# Dual_linear_VCA_chip_v3_0_-_external_tri.net
KiCad netlist of a schematic drawn in EAGLE
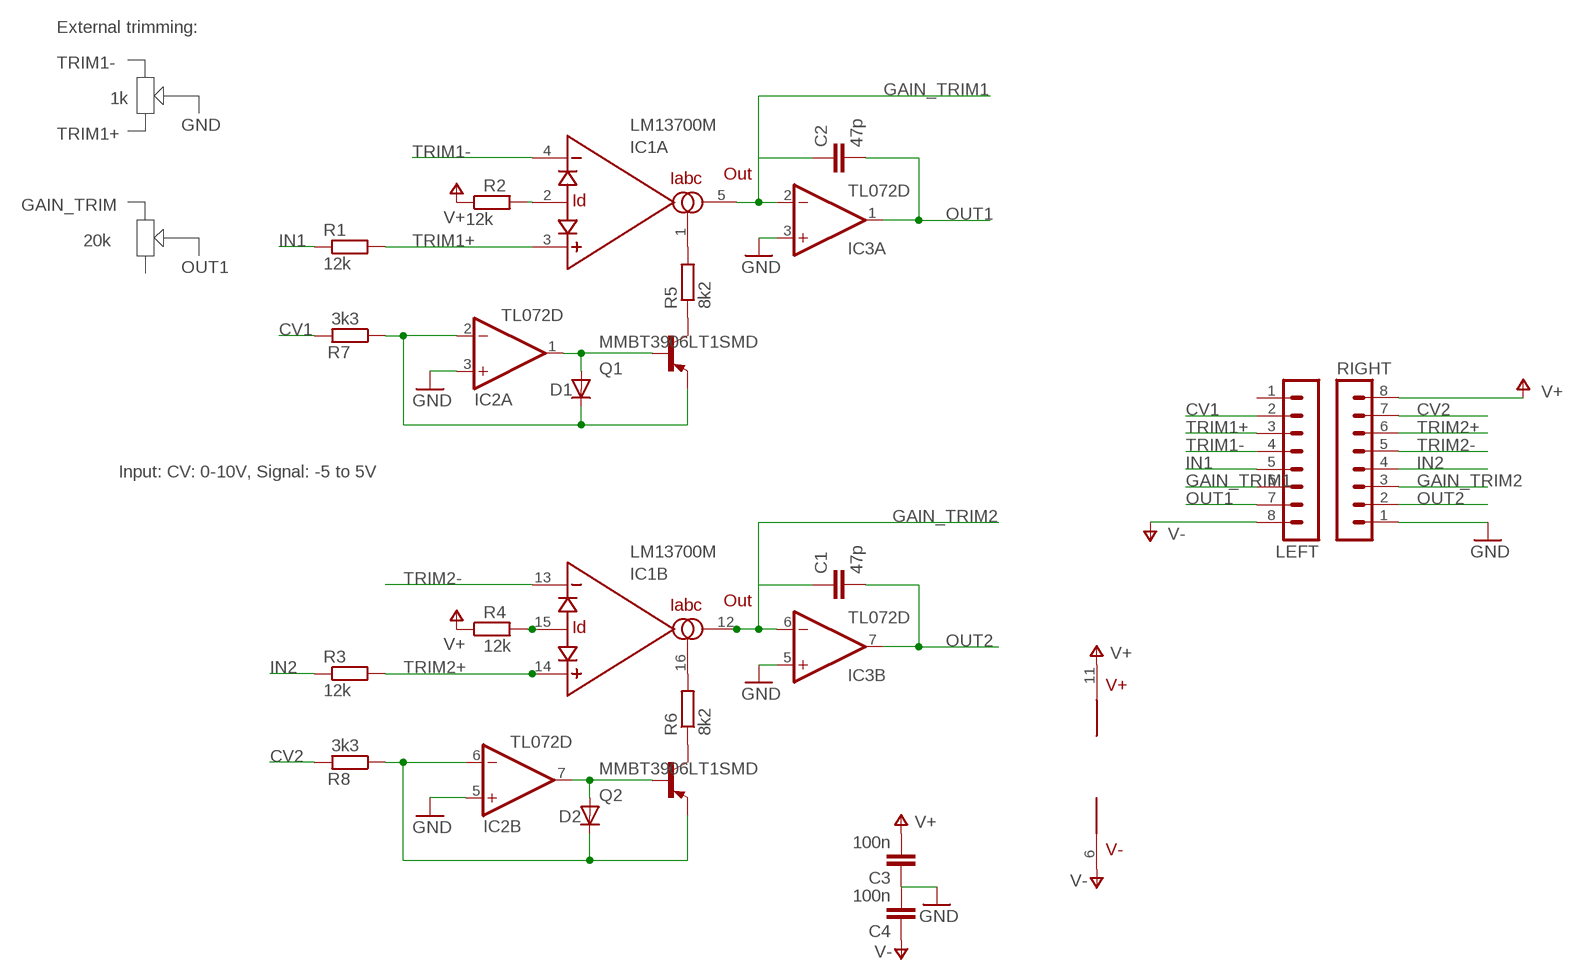
[diagram p0: schematic, sheet 1]

(export (version "E")
  (design (tool "Eeschema 10.0.6"))
  (components
    (comp (ref "C1")
      (value "47p")
      (footprint "eagle-import:C0805")
      (libsource (lib "eagle-import") (part "C-EUC0805"))
    )
    (comp (ref "C2")
      (value "47p")
      (footprint "eagle-import:C0805")
      (libsource (lib "eagle-import") (part "C-EUC0805"))
    )
    (comp (ref "C3")
      (value "100n")
      (footprint "eagle-import:C0805")
      (libsource (lib "eagle-import") (part "C-EUC0805"))
    )
    (comp (ref "C4")
      (value "100n")
      (footprint "eagle-import:C0805")
      (libsource (lib "eagle-import") (part "C-EUC0805"))
    )
    (comp (ref "D1")
      (value "DIODE-SOD80C")
      (footprint "eagle-import:SOD80C")
      (libsource (lib "eagle-import") (part "DIODE-SOD80C"))
    )
    (comp (ref "D2")
      (value "DIODE-SOD80C")
      (footprint "eagle-import:SOD80C")
      (libsource (lib "eagle-import") (part "DIODE-SOD80C"))
    )
    (comp (ref "IC1")
      (value "LM13700M")
      (footprint "eagle-import:SO16")
      (libsource (lib "eagle-import") (part "LM13700M"))
    )
    (comp (ref "IC2")
      (value "TL072D")
      (footprint "eagle-import:SO08")
      (libsource (lib "eagle-import") (part "TL072D"))
    )
    (comp (ref "IC3")
      (value "TL072D")
      (footprint "eagle-import:SO08")
      (libsource (lib "eagle-import") (part "TL072D"))
    )
    (comp (ref "LEFT")
      (value "MA08-1JC")
      (footprint "eagle-import:MA08-1J")
      (libsource (lib "eagle-import") (part "MA08-1JC"))
    )
    (comp (ref "Q1")
      (value "MMBT3906LT1SMD")
      (footprint "eagle-import:SOT23-BEC")
      (libsource (lib "eagle-import") (part "MMBT3906SMDLT1"))
    )
    (comp (ref "Q2")
      (value "MMBT3906LT1SMD")
      (footprint "eagle-import:SOT23-BEC")
      (libsource (lib "eagle-import") (part "MMBT3906SMDLT1"))
    )
    (comp (ref "R1")
      (value "12k")
      (footprint "eagle-import:R0805")
      (libsource (lib "eagle-import") (part "R-EU_R0805"))
    )
    (comp (ref "R2")
      (value "12k")
      (footprint "eagle-import:R0805")
      (libsource (lib "eagle-import") (part "R-EU_R0805"))
    )
    (comp (ref "R3")
      (value "12k")
      (footprint "eagle-import:R0805")
      (libsource (lib "eagle-import") (part "R-EU_R0805"))
    )
    (comp (ref "R4")
      (value "12k")
      (footprint "eagle-import:R0805")
      (libsource (lib "eagle-import") (part "R-EU_R0805"))
    )
    (comp (ref "R5")
      (value "8k2")
      (footprint "eagle-import:R0805")
      (libsource (lib "eagle-import") (part "R-EU_R0805"))
    )
    (comp (ref "R6")
      (value "8k2")
      (footprint "eagle-import:R0805")
      (libsource (lib "eagle-import") (part "R-EU_R0805"))
    )
    (comp (ref "R7")
      (value "3k3")
      (footprint "eagle-import:R0805")
      (libsource (lib "eagle-import") (part "R-EU_R0805"))
    )
    (comp (ref "R8")
      (value "3k3")
      (footprint "eagle-import:R0805")
      (libsource (lib "eagle-import") (part "R-EU_R0805"))
    )
    (comp (ref "RIGHT")
      (value "MA08-1JC")
      (footprint "eagle-import:MA08-1J")
      (libsource (lib "eagle-import") (part "MA08-1JC"))
    )
  )
  (nets
    (net (code "1") (name "/CV1") (class "Default")
      (node (ref "LEFT") (pin "2") (pinfunction "2_2") (pintype "passive"))
      (node (ref "R7") (pin "2") (pinfunction "2_2") (pintype "passive"))
    )
    (net (code "2") (name "/CV2") (class "Default")
      (node (ref "R8") (pin "2") (pinfunction "2_2") (pintype "passive"))
      (node (ref "RIGHT") (pin "7") (pinfunction "7_7") (pintype "passive"))
    )
    (net (code "3") (name "/GAIN_TRIM1") (class "Default")
      (node (ref "C2") (pin "1") (pinfunction "1_1") (pintype "passive"))
      (node (ref "IC1") (pin "5") (pinfunction "OUT_5") (pintype "bidirectional"))
      (node (ref "IC3") (pin "2") (pinfunction "-IN_2") (pintype "input"))
      (node (ref "LEFT") (pin "6") (pinfunction "6_6") (pintype "passive"))
    )
    (net (code "4") (name "/GAIN_TRIM2") (class "Default")
      (node (ref "C1") (pin "1") (pinfunction "1_1") (pintype "passive"))
      (node (ref "IC1") (pin "12") (pinfunction "OUT_12") (pintype "bidirectional"))
      (node (ref "IC3") (pin "6") (pinfunction "-IN_6") (pintype "input"))
      (node (ref "RIGHT") (pin "3") (pinfunction "3_3") (pintype "passive"))
    )
    (net (code "5") (name "/IN1") (class "Default")
      (node (ref "LEFT") (pin "5") (pinfunction "5_5") (pintype "passive"))
      (node (ref "R1") (pin "1") (pinfunction "1_1") (pintype "passive"))
    )
    (net (code "6") (name "/IN2") (class "Default")
      (node (ref "R3") (pin "1") (pinfunction "1_1") (pintype "passive"))
      (node (ref "RIGHT") (pin "4") (pinfunction "4_4") (pintype "passive"))
    )
    (net (code "7") (name "/OUT1") (class "Default")
      (node (ref "C2") (pin "2") (pinfunction "2_2") (pintype "passive"))
      (node (ref "IC3") (pin "1") (pinfunction "OUT_1") (pintype "output"))
      (node (ref "LEFT") (pin "7") (pinfunction "7_7") (pintype "passive"))
    )
    (net (code "8") (name "/OUT2") (class "Default")
      (node (ref "C1") (pin "2") (pinfunction "2_2") (pintype "passive"))
      (node (ref "IC3") (pin "7") (pinfunction "OUT_7") (pintype "output"))
      (node (ref "RIGHT") (pin "2") (pinfunction "2_2") (pintype "passive"))
    )
    (net (code "9") (name "/TRIM1+") (class "Default")
      (node (ref "IC1") (pin "3") (pinfunction "+IN_3") (pintype "bidirectional"))
      (node (ref "LEFT") (pin "3") (pinfunction "3_3") (pintype "passive"))
      (node (ref "R1") (pin "2") (pinfunction "2_2") (pintype "passive"))
    )
    (net (code "10") (name "/TRIM1-") (class "Default")
      (node (ref "IC1") (pin "4") (pinfunction "-IN_4") (pintype "bidirectional"))
      (node (ref "LEFT") (pin "4") (pinfunction "4_4") (pintype "passive"))
    )
    (net (code "11") (name "/TRIM2+") (class "Default")
      (node (ref "IC1") (pin "14") (pinfunction "+IN_14") (pintype "bidirectional"))
      (node (ref "R3") (pin "2") (pinfunction "2_2") (pintype "passive"))
      (node (ref "RIGHT") (pin "6") (pinfunction "6_6") (pintype "passive"))
    )
    (net (code "12") (name "/TRIM2-") (class "Default")
      (node (ref "IC1") (pin "13") (pinfunction "-IN_13") (pintype "bidirectional"))
      (node (ref "RIGHT") (pin "5") (pinfunction "5_5") (pintype "passive"))
    )
    (net (code "13") (name "GND") (class "Default")
      (node (ref "C3") (pin "1") (pinfunction "1_1") (pintype "passive"))
      (node (ref "C4") (pin "2") (pinfunction "2_2") (pintype "passive"))
      (node (ref "IC2") (pin "3") (pinfunction "+IN_3") (pintype "input"))
      (node (ref "IC2") (pin "5") (pinfunction "+IN_5") (pintype "input"))
      (node (ref "IC3") (pin "3") (pinfunction "+IN_3") (pintype "input"))
      (node (ref "IC3") (pin "5") (pinfunction "+IN_5") (pintype "input"))
      (node (ref "RIGHT") (pin "1") (pinfunction "1_1") (pintype "passive"))
    )
    (net (code "14") (name "Net-(IC1A-IABC)") (class "Default")
      (node (ref "IC1") (pin "1") (pinfunction "IABC_1") (pintype "bidirectional"))
      (node (ref "R5") (pin "2") (pinfunction "2_2") (pintype "passive"))
    )
    (net (code "15") (name "Net-(IC1A-ID)") (class "Default")
      (node (ref "IC1") (pin "2") (pinfunction "ID_2") (pintype "bidirectional"))
      (node (ref "R2") (pin "2") (pinfunction "2_2") (pintype "passive"))
    )
    (net (code "16") (name "Net-(IC1B-IABC)") (class "Default")
      (node (ref "IC1") (pin "16") (pinfunction "IABC_16") (pintype "bidirectional"))
      (node (ref "R6") (pin "2") (pinfunction "2_2") (pintype "passive"))
    )
    (net (code "17") (name "Net-(IC1B-ID)") (class "Default")
      (node (ref "IC1") (pin "15") (pinfunction "ID_15") (pintype "bidirectional"))
      (node (ref "R4") (pin "2") (pinfunction "2_2") (pintype "passive"))
    )
    (net (code "18") (name "Net-(IC2A--IN)") (class "Default")
      (node (ref "D1") (pin "C") (pinfunction "C_C") (pintype "passive"))
      (node (ref "IC2") (pin "2") (pinfunction "-IN_2") (pintype "input"))
      (node (ref "Q1") (pin "E") (pinfunction "E_E") (pintype "passive"))
      (node (ref "R7") (pin "1") (pinfunction "1_1") (pintype "passive"))
    )
    (net (code "19") (name "Net-(IC2A-OUT)") (class "Default")
      (node (ref "D1") (pin "A") (pinfunction "A_A") (pintype "passive"))
      (node (ref "IC2") (pin "1") (pinfunction "OUT_1") (pintype "output"))
      (node (ref "Q1") (pin "B") (pinfunction "B_B") (pintype "passive"))
    )
    (net (code "20") (name "Net-(IC2B--IN)") (class "Default")
      (node (ref "D2") (pin "C") (pinfunction "C_C") (pintype "passive"))
      (node (ref "IC2") (pin "6") (pinfunction "-IN_6") (pintype "input"))
      (node (ref "Q2") (pin "E") (pinfunction "E_E") (pintype "passive"))
      (node (ref "R8") (pin "1") (pinfunction "1_1") (pintype "passive"))
    )
    (net (code "21") (name "Net-(IC2B-OUT)") (class "Default")
      (node (ref "D2") (pin "A") (pinfunction "A_A") (pintype "passive"))
      (node (ref "IC2") (pin "7") (pinfunction "OUT_7") (pintype "output"))
      (node (ref "Q2") (pin "B") (pinfunction "B_B") (pintype "passive"))
    )
    (net (code "22") (name "Net-(Q1-PadC)") (class "Default")
      (node (ref "Q1") (pin "C") (pinfunction "C_C") (pintype "passive"))
      (node (ref "R5") (pin "1") (pinfunction "1_1") (pintype "passive"))
    )
    (net (code "23") (name "Net-(Q2-PadC)") (class "Default")
      (node (ref "Q2") (pin "C") (pinfunction "C_C") (pintype "passive"))
      (node (ref "R6") (pin "1") (pinfunction "1_1") (pintype "passive"))
    )
    (net (code "24") (name "V+") (class "Default")
      (node (ref "C3") (pin "2") (pinfunction "2_2") (pintype "passive"))
      (node (ref "IC1") (pin "11") (pinfunction "V+_11") (pintype "bidirectional"))
      (node (ref "R2") (pin "1") (pinfunction "1_1") (pintype "passive"))
      (node (ref "R4") (pin "1") (pinfunction "1_1") (pintype "passive"))
      (node (ref "RIGHT") (pin "8") (pinfunction "8_8") (pintype "passive"))
    )
    (net (code "25") (name "V-") (class "Default")
      (node (ref "C4") (pin "1") (pinfunction "1_1") (pintype "passive"))
      (node (ref "IC1") (pin "6") (pinfunction "V-_6") (pintype "bidirectional"))
      (node (ref "LEFT") (pin "8") (pinfunction "8_8") (pintype "passive"))
    )
    (net (code "26") (name "unconnected-(LEFT-Pad1)") (class "Default")
      (node (ref "LEFT") (pin "1") (pinfunction "1_1") (pintype "passive"))
    )
  )
)
